# EEPROM-Programmer.net
KiCad netlist of a schematic drawn in EAGLE
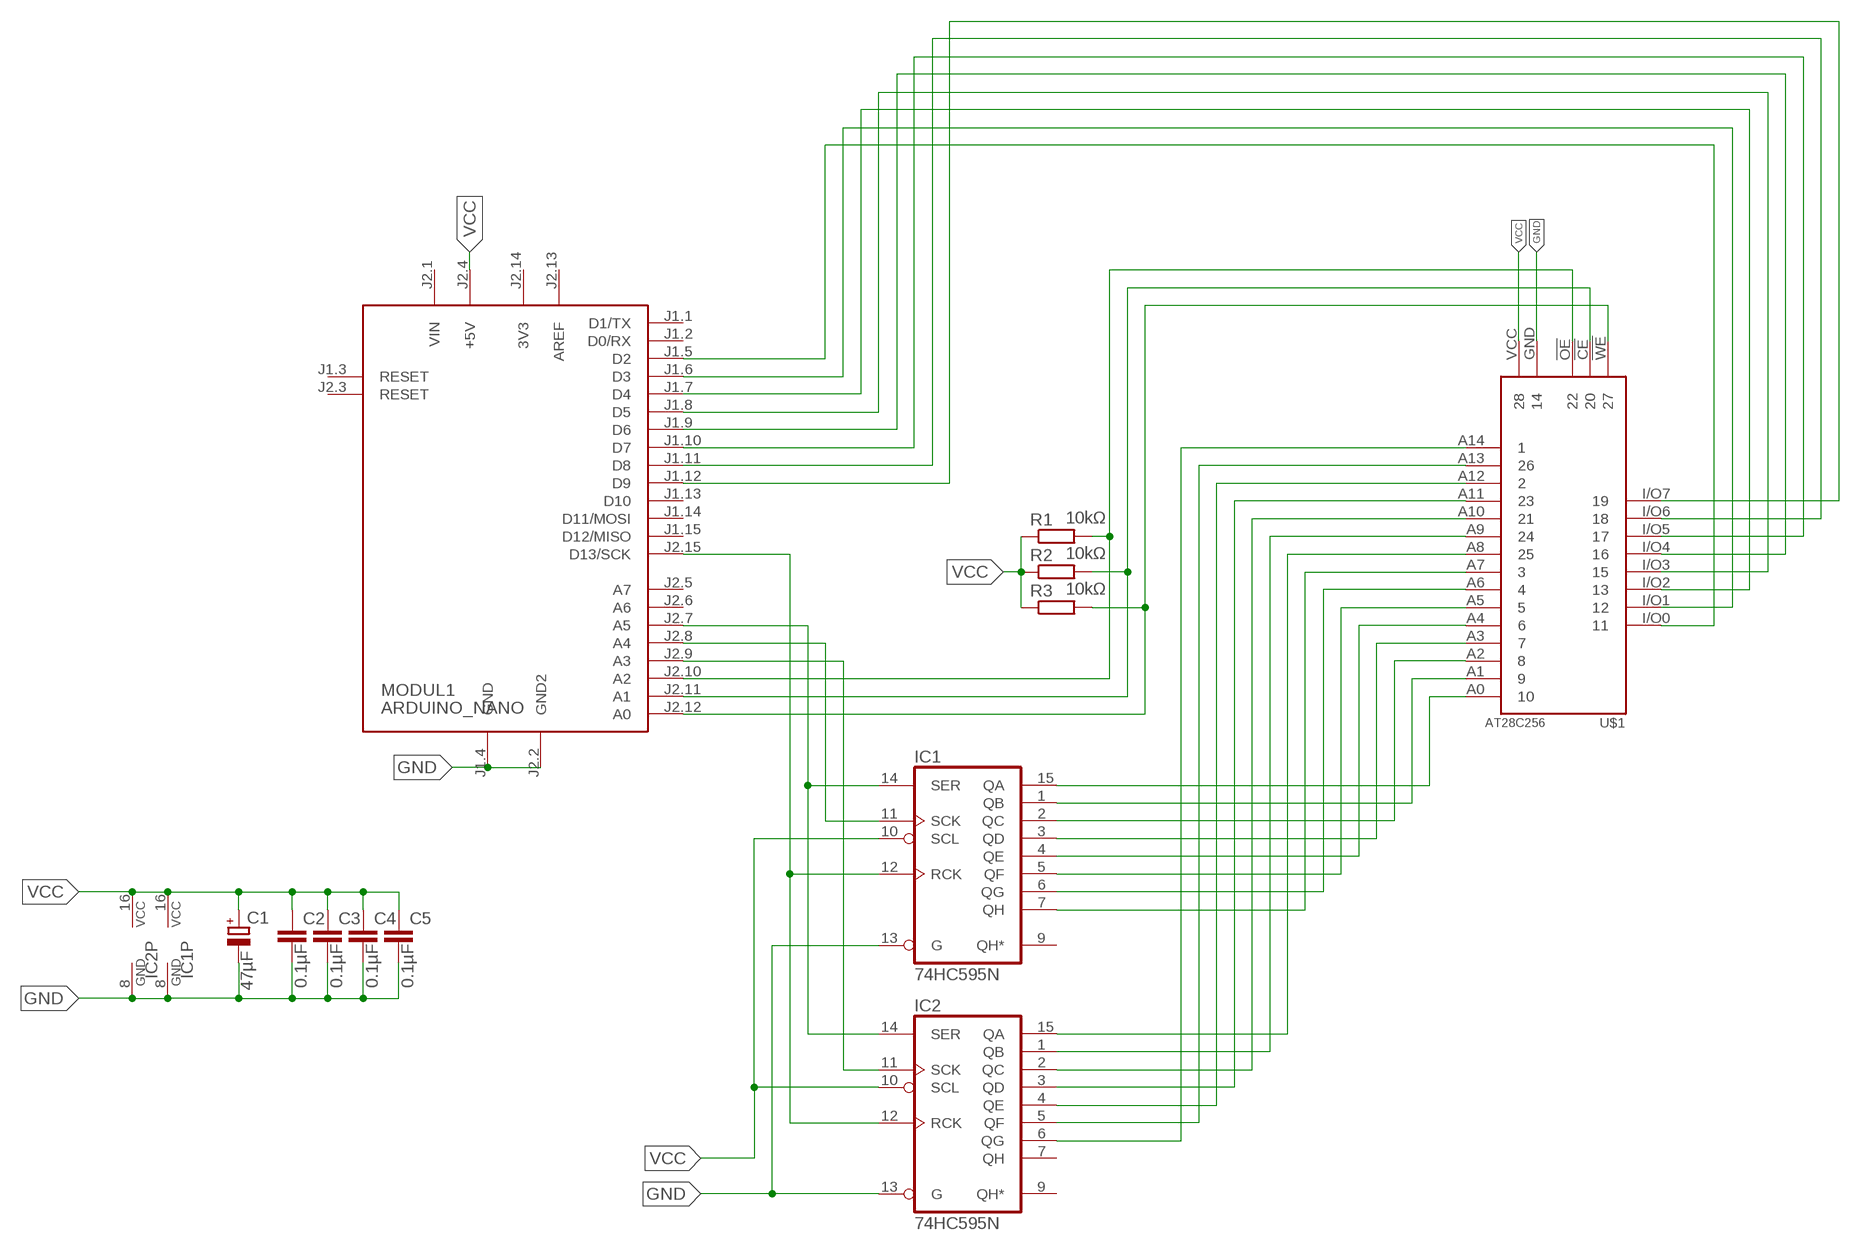
[diagram p0: schematic, sheet 1]

(export (version "E")
  (design (tool "Eeschema 10.0.6"))
  (components
    (comp (ref "C1")
      (value "47µF")
      (footprint "eagle-import:E2,5-6E")
      (libsource (lib "eagle-import") (part "CPOL-EUE2,5-6E"))
    )
    (comp (ref "C2")
      (value "0.1µF")
      (footprint "eagle-import:C2.5-3")
      (libsource (lib "eagle-import") (part "C2,5-3"))
    )
    (comp (ref "C3")
      (value "0.1µF")
      (footprint "eagle-import:C2.5-3")
      (libsource (lib "eagle-import") (part "C2,5-3"))
    )
    (comp (ref "C4")
      (value "0.1µF")
      (footprint "eagle-import:C2.5-3")
      (libsource (lib "eagle-import") (part "C2,5-3"))
    )
    (comp (ref "C5")
      (value "0.1µF")
      (footprint "eagle-import:C2.5-3")
      (libsource (lib "eagle-import") (part "C2,5-3"))
    )
    (comp (ref "IC1")
      (value "74HC595N")
      (footprint "eagle-import:DIL16")
      (libsource (lib "eagle-import") (part "74595NHC"))
    )
    (comp (ref "IC2")
      (value "74HC595N")
      (footprint "eagle-import:DIL16")
      (libsource (lib "eagle-import") (part "74595NHC"))
    )
    (comp (ref "MODUL1")
      (value "ARDUINO_NANO")
      (footprint "eagle-import:ARDUINO_NANO2")
      (libsource (lib "eagle-import") (part "ARDUINO_NANO"))
    )
    (comp (ref "R1")
      (value "10kΩ")
      (footprint "eagle-import:0204_7")
      (libsource (lib "eagle-import") (part "R-EU_0204/7"))
    )
    (comp (ref "R2")
      (value "10kΩ")
      (footprint "eagle-import:0204_7")
      (libsource (lib "eagle-import") (part "R-EU_0204/7"))
    )
    (comp (ref "R3")
      (value "10kΩ")
      (footprint "eagle-import:0204_7")
      (libsource (lib "eagle-import") (part "R-EU_0204/7"))
    )
    (comp (ref "U$1")
      (value "AT28C256")
      (footprint "eagle-import:AT28C256")
      (libsource (lib "eagle-import") (part "AT28C256"))
    )
  )
  (nets
    (net (code "1") (name "/3V3") (class "Default")
      (node (ref "MODUL1") (pin "J2.14") (pinfunction "3V3_J2.14") (pintype "power_in"))
    )
    (net (code "2") (name "/AREF") (class "Default")
      (node (ref "MODUL1") (pin "J2.13") (pinfunction "AREF_J2.13") (pintype "power_in"))
    )
    (net (code "3") (name "/VIN") (class "Default")
      (node (ref "MODUL1") (pin "J2.1") (pinfunction "VIN_J2.1") (pintype "power_in"))
    )
    (net (code "4") (name "GND") (class "Default")
      (node (ref "C1") (pin "-") (pinfunction "-_-") (pintype "passive"))
      (node (ref "C2") (pin "2") (pinfunction "2_2") (pintype "passive"))
      (node (ref "C3") (pin "2") (pinfunction "2_2") (pintype "passive"))
      (node (ref "C4") (pin "2") (pinfunction "2_2") (pintype "passive"))
      (node (ref "C5") (pin "2") (pinfunction "2_2") (pintype "passive"))
      (node (ref "IC1") (pin "13") (pinfunction "G_13") (pintype "input"))
      (node (ref "IC1") (pin "8") (pinfunction "GND_8") (pintype "power_in"))
      (node (ref "IC2") (pin "13") (pinfunction "G_13") (pintype "input"))
      (node (ref "IC2") (pin "8") (pinfunction "GND_8") (pintype "power_in"))
      (node (ref "MODUL1") (pin "J1.4") (pinfunction "GND_J1.4") (pintype "power_in"))
      (node (ref "MODUL1") (pin "J2.2") (pinfunction "GND2_J2.2") (pintype "power_in"))
      (node (ref "U$1") (pin "GND") (pinfunction "14_GND") (pintype "bidirectional"))
    )
    (net (code "5") (name "Net-(IC1A-QA)") (class "Default")
      (node (ref "IC1") (pin "15") (pinfunction "QA_15") (pintype "tri_state"))
      (node (ref "U$1") (pin "A0") (pinfunction "10_A0") (pintype "bidirectional"))
    )
    (net (code "6") (name "Net-(IC1A-QB)") (class "Default")
      (node (ref "IC1") (pin "1") (pinfunction "QB_1") (pintype "tri_state"))
      (node (ref "U$1") (pin "A1") (pinfunction "9_A1") (pintype "bidirectional"))
    )
    (net (code "7") (name "Net-(IC1A-QC)") (class "Default")
      (node (ref "IC1") (pin "2") (pinfunction "QC_2") (pintype "tri_state"))
      (node (ref "U$1") (pin "A2") (pinfunction "8_A2") (pintype "bidirectional"))
    )
    (net (code "8") (name "Net-(IC1A-QD)") (class "Default")
      (node (ref "IC1") (pin "3") (pinfunction "QD_3") (pintype "tri_state"))
      (node (ref "U$1") (pin "A3") (pinfunction "7_A3") (pintype "bidirectional"))
    )
    (net (code "9") (name "Net-(IC1A-QE)") (class "Default")
      (node (ref "IC1") (pin "4") (pinfunction "QE_4") (pintype "tri_state"))
      (node (ref "U$1") (pin "A4") (pinfunction "6_A4") (pintype "bidirectional"))
    )
    (net (code "10") (name "Net-(IC1A-QF)") (class "Default")
      (node (ref "IC1") (pin "5") (pinfunction "QF_5") (pintype "tri_state"))
      (node (ref "U$1") (pin "A5") (pinfunction "5_A5") (pintype "bidirectional"))
    )
    (net (code "11") (name "Net-(IC1A-QG)") (class "Default")
      (node (ref "IC1") (pin "6") (pinfunction "QG_6") (pintype "tri_state"))
      (node (ref "U$1") (pin "A6") (pinfunction "4_A6") (pintype "bidirectional"))
    )
    (net (code "12") (name "Net-(IC1A-QH)") (class "Default")
      (node (ref "IC1") (pin "7") (pinfunction "QH_7") (pintype "tri_state"))
      (node (ref "U$1") (pin "A7") (pinfunction "3_A7") (pintype "bidirectional"))
    )
    (net (code "13") (name "Net-(IC1A-RCK)") (class "Default")
      (node (ref "IC1") (pin "12") (pinfunction "RCK_12") (pintype "input"))
      (node (ref "IC2") (pin "12") (pinfunction "RCK_12") (pintype "input"))
      (node (ref "MODUL1") (pin "J2.15") (pinfunction "D13/SCK_J2.15") (pintype "bidirectional"))
    )
    (net (code "14") (name "Net-(IC1A-SCK)") (class "Default")
      (node (ref "IC1") (pin "11") (pinfunction "SCK_11") (pintype "input"))
      (node (ref "MODUL1") (pin "J2.8") (pinfunction "A4_J2.8") (pintype "bidirectional"))
    )
    (net (code "15") (name "Net-(IC1A-SER)") (class "Default")
      (node (ref "IC1") (pin "14") (pinfunction "SER_14") (pintype "input"))
      (node (ref "IC2") (pin "14") (pinfunction "SER_14") (pintype "input"))
      (node (ref "MODUL1") (pin "J2.7") (pinfunction "A5_J2.7") (pintype "bidirectional"))
    )
    (net (code "16") (name "Net-(IC2A-QA)") (class "Default")
      (node (ref "IC2") (pin "15") (pinfunction "QA_15") (pintype "tri_state"))
      (node (ref "U$1") (pin "A8") (pinfunction "25_A8") (pintype "bidirectional"))
    )
    (net (code "17") (name "Net-(IC2A-QB)") (class "Default")
      (node (ref "IC2") (pin "1") (pinfunction "QB_1") (pintype "tri_state"))
      (node (ref "U$1") (pin "A9") (pinfunction "24_A9") (pintype "bidirectional"))
    )
    (net (code "18") (name "Net-(IC2A-QC)") (class "Default")
      (node (ref "IC2") (pin "2") (pinfunction "QC_2") (pintype "tri_state"))
      (node (ref "U$1") (pin "A10") (pinfunction "21_A10") (pintype "bidirectional"))
    )
    (net (code "19") (name "Net-(IC2A-QD)") (class "Default")
      (node (ref "IC2") (pin "3") (pinfunction "QD_3") (pintype "tri_state"))
      (node (ref "U$1") (pin "A11") (pinfunction "23_A11") (pintype "bidirectional"))
    )
    (net (code "20") (name "Net-(IC2A-QE)") (class "Default")
      (node (ref "IC2") (pin "4") (pinfunction "QE_4") (pintype "tri_state"))
      (node (ref "U$1") (pin "A12") (pinfunction "2_A12") (pintype "bidirectional"))
    )
    (net (code "21") (name "Net-(IC2A-QF)") (class "Default")
      (node (ref "IC2") (pin "5") (pinfunction "QF_5") (pintype "tri_state"))
      (node (ref "U$1") (pin "A13") (pinfunction "26_A13") (pintype "bidirectional"))
    )
    (net (code "22") (name "Net-(IC2A-QG)") (class "Default")
      (node (ref "IC2") (pin "6") (pinfunction "QG_6") (pintype "tri_state"))
      (node (ref "U$1") (pin "A14") (pinfunction "1_A14") (pintype "bidirectional"))
    )
    (net (code "23") (name "Net-(IC2A-SCK)") (class "Default")
      (node (ref "IC2") (pin "11") (pinfunction "SCK_11") (pintype "input"))
      (node (ref "MODUL1") (pin "J2.9") (pinfunction "A3_J2.9") (pintype "bidirectional"))
    )
    (net (code "24") (name "Net-(MODUL1-A0)") (class "Default")
      (node (ref "MODUL1") (pin "J2.12") (pinfunction "A0_J2.12") (pintype "bidirectional"))
      (node (ref "R3") (pin "2") (pinfunction "2_2") (pintype "passive"))
      (node (ref "U$1") (pin "!WE") (pinfunction "27_!WE") (pintype "bidirectional"))
    )
    (net (code "25") (name "Net-(MODUL1-A1)") (class "Default")
      (node (ref "MODUL1") (pin "J2.11") (pinfunction "A1_J2.11") (pintype "bidirectional"))
      (node (ref "R2") (pin "2") (pinfunction "2_2") (pintype "passive"))
      (node (ref "U$1") (pin "!CE") (pinfunction "20_!CE") (pintype "bidirectional"))
    )
    (net (code "26") (name "Net-(MODUL1-A2)") (class "Default")
      (node (ref "MODUL1") (pin "J2.10") (pinfunction "A2_J2.10") (pintype "bidirectional"))
      (node (ref "R1") (pin "2") (pinfunction "2_2") (pintype "passive"))
      (node (ref "U$1") (pin "!OE") (pinfunction "22_!OE") (pintype "bidirectional"))
    )
    (net (code "27") (name "Net-(MODUL1-D2)") (class "Default")
      (node (ref "MODUL1") (pin "J1.5") (pinfunction "D2_J1.5") (pintype "bidirectional"))
      (node (ref "U$1") (pin "I/O0") (pinfunction "11_I/O0") (pintype "bidirectional"))
    )
    (net (code "28") (name "Net-(MODUL1-D3)") (class "Default")
      (node (ref "MODUL1") (pin "J1.6") (pinfunction "D3_J1.6") (pintype "bidirectional"))
      (node (ref "U$1") (pin "I/O1") (pinfunction "12_I/O1") (pintype "bidirectional"))
    )
    (net (code "29") (name "Net-(MODUL1-D4)") (class "Default")
      (node (ref "MODUL1") (pin "J1.7") (pinfunction "D4_J1.7") (pintype "bidirectional"))
      (node (ref "U$1") (pin "I/O2") (pinfunction "13_I/O2") (pintype "bidirectional"))
    )
    (net (code "30") (name "Net-(MODUL1-D5)") (class "Default")
      (node (ref "MODUL1") (pin "J1.8") (pinfunction "D5_J1.8") (pintype "bidirectional"))
      (node (ref "U$1") (pin "I/O3") (pinfunction "15_I/O3") (pintype "bidirectional"))
    )
    (net (code "31") (name "Net-(MODUL1-D6)") (class "Default")
      (node (ref "MODUL1") (pin "J1.9") (pinfunction "D6_J1.9") (pintype "bidirectional"))
      (node (ref "U$1") (pin "I/O4") (pinfunction "16_I/O4") (pintype "bidirectional"))
    )
    (net (code "32") (name "Net-(MODUL1-D7)") (class "Default")
      (node (ref "MODUL1") (pin "J1.10") (pinfunction "D7_J1.10") (pintype "bidirectional"))
      (node (ref "U$1") (pin "I/O5") (pinfunction "17_I/O5") (pintype "bidirectional"))
    )
    (net (code "33") (name "Net-(MODUL1-D8)") (class "Default")
      (node (ref "MODUL1") (pin "J1.11") (pinfunction "D8_J1.11") (pintype "bidirectional"))
      (node (ref "U$1") (pin "I/O6") (pinfunction "18_I/O6") (pintype "bidirectional"))
    )
    (net (code "34") (name "Net-(MODUL1-D9)") (class "Default")
      (node (ref "MODUL1") (pin "J1.12") (pinfunction "D9_J1.12") (pintype "bidirectional"))
      (node (ref "U$1") (pin "I/O7") (pinfunction "19_I/O7") (pintype "bidirectional"))
    )
    (net (code "35") (name "VCC") (class "Default")
      (node (ref "C1") (pin "+") (pinfunction "+_+") (pintype "passive"))
      (node (ref "C2") (pin "1") (pinfunction "1_1") (pintype "passive"))
      (node (ref "C3") (pin "1") (pinfunction "1_1") (pintype "passive"))
      (node (ref "C4") (pin "1") (pinfunction "1_1") (pintype "passive"))
      (node (ref "C5") (pin "1") (pinfunction "1_1") (pintype "passive"))
      (node (ref "IC1") (pin "10") (pinfunction "SCL_10") (pintype "input"))
      (node (ref "IC1") (pin "16") (pinfunction "VCC_16") (pintype "power_in"))
      (node (ref "IC2") (pin "10") (pinfunction "SCL_10") (pintype "input"))
      (node (ref "IC2") (pin "16") (pinfunction "VCC_16") (pintype "power_in"))
      (node (ref "MODUL1") (pin "J2.4") (pinfunction "+5V_J2.4") (pintype "power_in"))
      (node (ref "R1") (pin "1") (pinfunction "1_1") (pintype "passive"))
      (node (ref "R2") (pin "1") (pinfunction "1_1") (pintype "passive"))
      (node (ref "R3") (pin "1") (pinfunction "1_1") (pintype "passive"))
      (node (ref "U$1") (pin "VCC") (pinfunction "28_VCC") (pintype "bidirectional"))
    )
    (net (code "36") (name "unconnected-(IC1A-QH*-Pad9)") (class "Default")
      (node (ref "IC1") (pin "9") (pinfunction "QH*_9") (pintype "tri_state"))
    )
    (net (code "37") (name "unconnected-(IC2A-QH*-Pad9)") (class "Default")
      (node (ref "IC2") (pin "9") (pinfunction "QH*_9") (pintype "tri_state"))
    )
    (net (code "38") (name "unconnected-(IC2A-QH-Pad7)") (class "Default")
      (node (ref "IC2") (pin "7") (pinfunction "QH_7") (pintype "tri_state"))
    )
    (net (code "39") (name "unconnected-(MODUL1-A6-PadJ2.6)") (class "Default")
      (node (ref "MODUL1") (pin "J2.6") (pinfunction "A6_J2.6") (pintype "bidirectional"))
    )
    (net (code "40") (name "unconnected-(MODUL1-A7-PadJ2.5)") (class "Default")
      (node (ref "MODUL1") (pin "J2.5") (pinfunction "A7_J2.5") (pintype "bidirectional"))
    )
    (net (code "41") (name "unconnected-(MODUL1-D0{slash}RX-PadJ1.2)") (class "Default")
      (node (ref "MODUL1") (pin "J1.2") (pinfunction "D0/RX_J1.2") (pintype "bidirectional"))
    )
    (net (code "42") (name "unconnected-(MODUL1-D1{slash}TX-PadJ1.1)") (class "Default")
      (node (ref "MODUL1") (pin "J1.1") (pinfunction "D1/TX_J1.1") (pintype "bidirectional"))
    )
    (net (code "43") (name "unconnected-(MODUL1-D10-PadJ1.13)") (class "Default")
      (node (ref "MODUL1") (pin "J1.13") (pinfunction "D10_J1.13") (pintype "bidirectional"))
    )
    (net (code "44") (name "unconnected-(MODUL1-D11{slash}MOSI-PadJ1.14)") (class "Default")
      (node (ref "MODUL1") (pin "J1.14") (pinfunction "D11/MOSI_J1.14") (pintype "bidirectional"))
    )
    (net (code "45") (name "unconnected-(MODUL1-D12{slash}MISO-PadJ1.15)") (class "Default")
      (node (ref "MODUL1") (pin "J1.15") (pinfunction "D12/MISO_J1.15") (pintype "bidirectional"))
    )
    (net (code "46") (name "unconnected-(MODUL1-RESET-PadJ1.3)") (class "Default")
      (node (ref "MODUL1") (pin "J1.3") (pinfunction "RESET_J1.3") (pintype "bidirectional"))
    )
    (net (code "47") (name "unconnected-(MODUL1-RESET-PadJ2.3)") (class "Default")
      (node (ref "MODUL1") (pin "J2.3") (pinfunction "RESET_J2.3") (pintype "bidirectional"))
    )
  )
)
